# Schematic.net
KiCad netlist of a schematic drawn in EAGLE
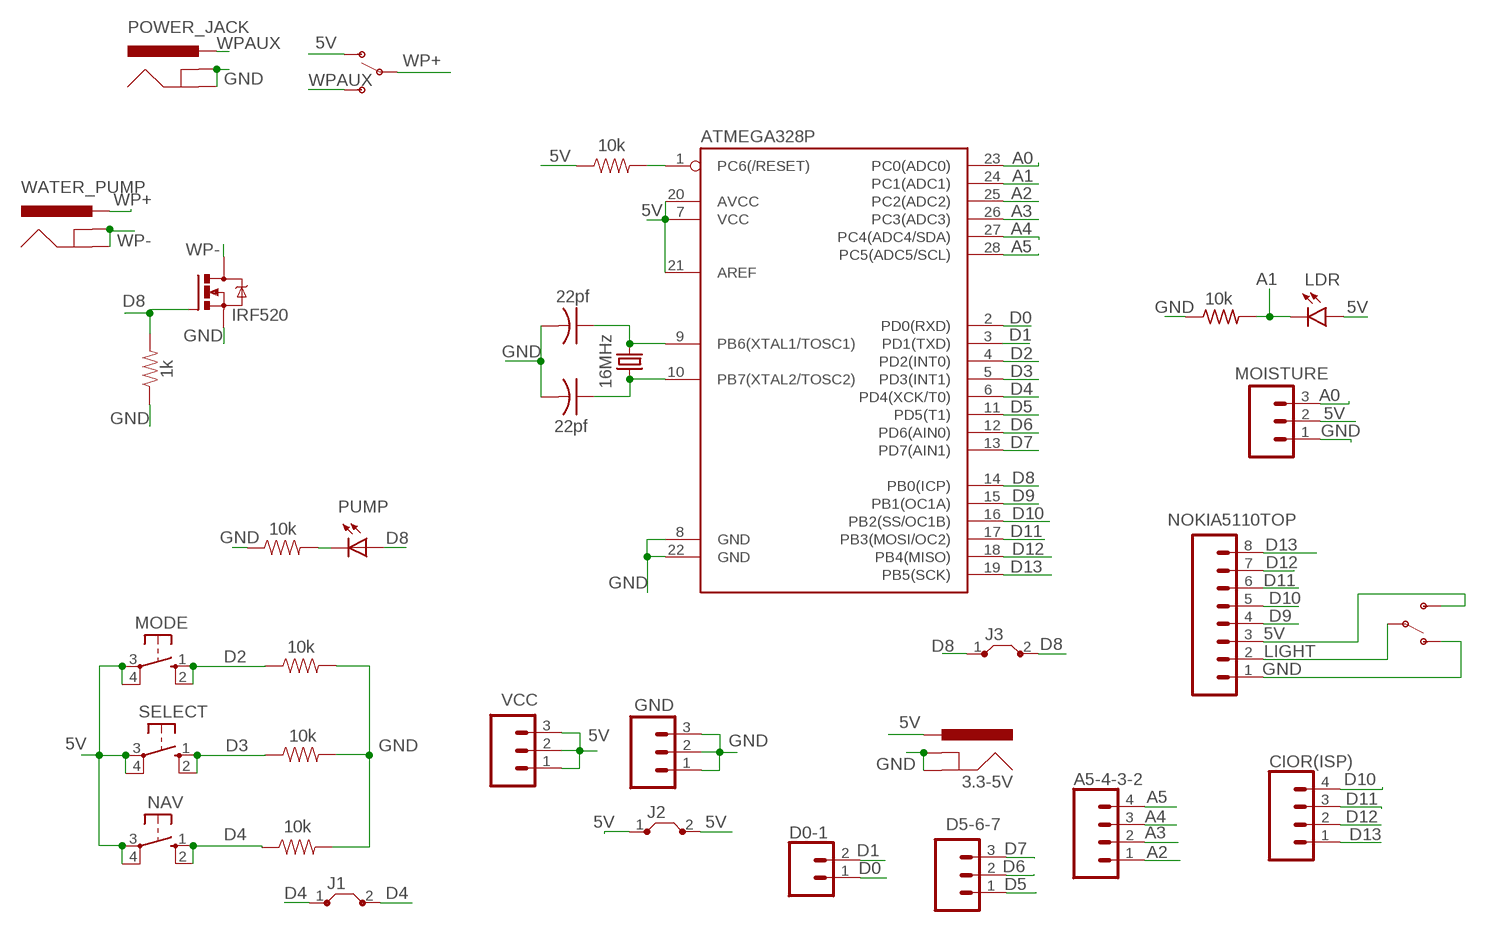
[diagram p0: schematic, sheet 1]

(export (version "E")
  (design (tool "Eeschema 10.0.6"))
  (components
    (comp (ref "3.3-5V")
      (value "POWER_JACK")
      (footprint "eagle-import:POWER_JACK_PTH")
      (libsource (lib "eagle-import") (part "POWER_JACK"))
    )
    (comp (ref "5V/AUX")
      (value "SWITCH-SPDT-PTH-11.6X4.0MM-LOCK")
      (footprint "eagle-import:SWITCH_SPDT_PTH_11.6X4.0MM_LOCK")
      (libsource (lib "eagle-import") (part "SWITCH-SPDT-PTH-11.6X4.0MM-LOCK"))
    )
    (comp (ref "A5-4-3-2")
      (value "CONN_04")
      (footprint "eagle-import:1X04")
      (libsource (lib "eagle-import") (part "CONN_04"))
    )
    (comp (ref "ATMEGA328P")
      (value "328P")
      (footprint "eagle-import:DIP28")
      (libsource (lib "eagle-import") (part "ATMEGA328P_PDIP"))
    )
    (comp (ref "AUX_POWER")
      (value "POWER_JACK")
      (footprint "eagle-import:POWER_JACK_PTH")
      (libsource (lib "eagle-import") (part "POWER_JACK"))
    )
    (comp (ref "C1")
      (value "22pf")
      (footprint "eagle-import:C025-024X044")
      (libsource (lib "eagle-import") (part "C-US025-024X044"))
    )
    (comp (ref "C2")
      (value "22pf")
      (footprint "eagle-import:C025-024X044")
      (libsource (lib "eagle-import") (part "C-US025-024X044"))
    )
    (comp (ref "CIOR(ISP)")
      (value "CONN_04")
      (footprint "eagle-import:1X04")
      (libsource (lib "eagle-import") (part "CONN_04"))
    )
    (comp (ref "D0-1")
      (value "CONN_02")
      (footprint "eagle-import:1X02")
      (libsource (lib "eagle-import") (part "CONN_02"))
    )
    (comp (ref "D5-6-7")
      (value "CONN_03")
      (footprint "eagle-import:1X03")
      (libsource (lib "eagle-import") (part "CONN_03"))
    )
    (comp (ref "GND")
      (value "CONN_03")
      (footprint "eagle-import:1X03")
      (libsource (lib "eagle-import") (part "CONN_03"))
    )
    (comp (ref "GND/VCC")
      (value "SWITCH-SPDT-PTH-11.6X4.0MM-LOCK")
      (footprint "eagle-import:SWITCH_SPDT_PTH_11.6X4.0MM_LOCK")
      (libsource (lib "eagle-import") (part "SWITCH-SPDT-PTH-11.6X4.0MM-LOCK"))
    )
    (comp (ref "J1")
      (value "J5MM")
      (footprint "eagle-import:05")
      (libsource (lib "eagle-import") (part "J5MM"))
    )
    (comp (ref "J2")
      (value "J5MM")
      (footprint "eagle-import:05")
      (libsource (lib "eagle-import") (part "J5MM"))
    )
    (comp (ref "J3")
      (value "J5MM")
      (footprint "eagle-import:05")
      (libsource (lib "eagle-import") (part "J5MM"))
    )
    (comp (ref "LDR")
      (value "LED3MM")
      (footprint "eagle-import:LED_3MM")
      (libsource (lib "eagle-import") (part "LED3MM"))
    )
    (comp (ref "MODE")
      (value "10-XX")
      (footprint "eagle-import:B3F-10XX")
      (fields (field (name "MPN") "B3F-1000"))
      (libsource (lib "eagle-import") (part "10-XX"))
    )
    (comp (ref "MOISTURE")
      (value "CONN_03")
      (footprint "eagle-import:1X03")
      (libsource (lib "eagle-import") (part "CONN_03"))
    )
    (comp (ref "NAV")
      (value "10-XX")
      (footprint "eagle-import:B3F-10XX")
      (fields (field (name "MPN") "B3F-1000"))
      (libsource (lib "eagle-import") (part "10-XX"))
    )
    (comp (ref "NOKIA5110TOP")
      (value "CONN_08\"")
      (footprint "eagle-import:1X08")
      (libsource (lib "eagle-import") (part "CONN_08{dblquote}"))
    )
    (comp (ref "PUMP")
      (value "LED5MM")
      (footprint "eagle-import:LED5MM")
      (libsource (lib "eagle-import") (part "adafruit_420_LED5MM"))
    )
    (comp (ref "Q1")
      (value "IRF520")
      (footprint "eagle-import:TO220BV")
      (libsource (lib "eagle-import") (part "IRF520"))
    )
    (comp (ref "R2")
      (value "10k")
      (footprint "eagle-import:AXIAL-0.1")
      (libsource (lib "eagle-import") (part "10KOHM-VERT-1/4W-5%"))
    )
    (comp (ref "R3")
      (value "10k")
      (footprint "eagle-import:AXIAL-0.1")
      (libsource (lib "eagle-import") (part "10KOHM-VERT-1/6W-5%"))
    )
    (comp (ref "R4")
      (value "10k")
      (footprint "eagle-import:AXIAL-0.1")
      (libsource (lib "eagle-import") (part "10KOHM-VERT-1/6W-5%"))
    )
    (comp (ref "R5")
      (value "10k")
      (footprint "eagle-import:AXIAL-0.1")
      (libsource (lib "eagle-import") (part "10KOHM-VERT-1/6W-5%"))
    )
    (comp (ref "R6")
      (value "10k")
      (footprint "eagle-import:0207_2V")
      (libsource (lib "eagle-import") (part "R-US_0207/2V"))
    )
    (comp (ref "R7")
      (value "10k")
      (footprint "eagle-import:AXIAL-0.1")
      (libsource (lib "eagle-import") (part "10KOHM-VERT-1/6W-5%"))
    )
    (comp (ref "R8")
      (value "1k")
      (footprint "eagle-import:AXIAL-0.1")
      (libsource (lib "eagle-import") (part "1KOHM-VERT-1/6W-5%"))
    )
    (comp (ref "SELECT")
      (value "10-XX")
      (footprint "eagle-import:B3F-10XX")
      (fields (field (name "MPN") "B3F-1000"))
      (libsource (lib "eagle-import") (part "10-XX"))
    )
    (comp (ref "VCC")
      (value "CONN_03")
      (footprint "eagle-import:1X03")
      (libsource (lib "eagle-import") (part "CONN_03"))
    )
    (comp (ref "WATER_PUMP")
      (value "WATER_PUMP")
      (footprint "eagle-import:POWER_JACK_PTH")
      (libsource (lib "eagle-import") (part "POWER_JACK"))
    )
    (comp (ref "Y1")
      (value "16MHz")
      (footprint "eagle-import:HC49US")
      (libsource (lib "eagle-import") (part "CRYSTAL-16MHZPTH-HC49US"))
    )
  )
  (nets
    (net (code "1") (name "/5V") (class "Default")
      (node (ref "3.3-5V") (pin "PWR") (pinfunction "PWR_PWR") (pintype "bidirectional"))
      (node (ref "5V/AUX") (pin "1") (pinfunction "O_1") (pintype "passive"))
      (node (ref "ATMEGA328P") (pin "20") (pinfunction "AVCC_20") (pintype "bidirectional"))
      (node (ref "ATMEGA328P") (pin "21") (pinfunction "AREF_21") (pintype "bidirectional"))
      (node (ref "ATMEGA328P") (pin "7") (pinfunction "VCC_7") (pintype "bidirectional"))
      (node (ref "GND/VCC") (pin "3") (pinfunction "S_3") (pintype "passive"))
      (node (ref "J2") (pin "1") (pinfunction "1_1") (pintype "passive"))
      (node (ref "J2") (pin "2") (pinfunction "2_2") (pintype "passive"))
      (node (ref "LDR") (pin "A") (pinfunction "A_A") (pintype "passive"))
      (node (ref "MODE") (pin "3") (pinfunction "P_3") (pintype "passive"))
      (node (ref "MODE") (pin "4") (pinfunction "P1_4") (pintype "passive"))
      (node (ref "MOISTURE") (pin "2") (pinfunction "2_2") (pintype "passive"))
      (node (ref "NAV") (pin "3") (pinfunction "P_3") (pintype "passive"))
      (node (ref "NAV") (pin "4") (pinfunction "P1_4") (pintype "passive"))
      (node (ref "NOKIA5110TOP") (pin "3") (pinfunction "3_3") (pintype "passive"))
      (node (ref "R7") (pin "P$1") (pinfunction "1_P$1") (pintype "passive"))
      (node (ref "SELECT") (pin "3") (pinfunction "P_3") (pintype "passive"))
      (node (ref "SELECT") (pin "4") (pinfunction "P1_4") (pintype "passive"))
      (node (ref "VCC") (pin "1") (pinfunction "1_1") (pintype "passive"))
      (node (ref "VCC") (pin "2") (pinfunction "2_2") (pintype "passive"))
      (node (ref "VCC") (pin "3") (pinfunction "3_3") (pintype "passive"))
    )
    (net (code "2") (name "/A0") (class "Default")
      (node (ref "ATMEGA328P") (pin "23") (pinfunction "PC0(ADC0)_23") (pintype "bidirectional"))
      (node (ref "MOISTURE") (pin "3") (pinfunction "3_3") (pintype "passive"))
    )
    (net (code "3") (name "/A1") (class "Default")
      (node (ref "ATMEGA328P") (pin "24") (pinfunction "PC1(ADC1)_24") (pintype "bidirectional"))
      (node (ref "LDR") (pin "K") (pinfunction "C_K") (pintype "passive"))
      (node (ref "R6") (pin "2") (pinfunction "2_2") (pintype "passive"))
    )
    (net (code "4") (name "/A2") (class "Default")
      (node (ref "A5-4-3-2") (pin "1") (pinfunction "1_1") (pintype "passive"))
      (node (ref "ATMEGA328P") (pin "25") (pinfunction "PC2(ADC2)_25") (pintype "bidirectional"))
    )
    (net (code "5") (name "/A3") (class "Default")
      (node (ref "A5-4-3-2") (pin "2") (pinfunction "2_2") (pintype "passive"))
      (node (ref "ATMEGA328P") (pin "26") (pinfunction "PC3(ADC3)_26") (pintype "bidirectional"))
    )
    (net (code "6") (name "/A4") (class "Default")
      (node (ref "A5-4-3-2") (pin "3") (pinfunction "3_3") (pintype "passive"))
      (node (ref "ATMEGA328P") (pin "27") (pinfunction "PC4(ADC4/SDA)_27") (pintype "bidirectional"))
    )
    (net (code "7") (name "/A5") (class "Default")
      (node (ref "A5-4-3-2") (pin "4") (pinfunction "4_4") (pintype "passive"))
      (node (ref "ATMEGA328P") (pin "28") (pinfunction "PC5(ADC5/SCL)_28") (pintype "bidirectional"))
    )
    (net (code "8") (name "/D0") (class "Default")
      (node (ref "ATMEGA328P") (pin "2") (pinfunction "PD0(RXD)_2") (pintype "bidirectional"))
      (node (ref "D0-1") (pin "1") (pinfunction "1_1") (pintype "passive"))
    )
    (net (code "9") (name "/D1") (class "Default")
      (node (ref "ATMEGA328P") (pin "3") (pinfunction "PD1(TXD)_3") (pintype "bidirectional"))
      (node (ref "D0-1") (pin "2") (pinfunction "2_2") (pintype "passive"))
    )
    (net (code "10") (name "/D2") (class "Default")
      (node (ref "ATMEGA328P") (pin "4") (pinfunction "PD2(INT0)_4") (pintype "bidirectional"))
      (node (ref "MODE") (pin "1") (pinfunction "S_1") (pintype "passive"))
      (node (ref "MODE") (pin "2") (pinfunction "S1_2") (pintype "passive"))
      (node (ref "R5") (pin "P$1") (pinfunction "1_P$1") (pintype "passive"))
    )
    (net (code "11") (name "/D3") (class "Default")
      (node (ref "ATMEGA328P") (pin "5") (pinfunction "PD3(INT1)_5") (pintype "bidirectional"))
      (node (ref "R4") (pin "P$1") (pinfunction "1_P$1") (pintype "passive"))
      (node (ref "SELECT") (pin "1") (pinfunction "S_1") (pintype "passive"))
      (node (ref "SELECT") (pin "2") (pinfunction "S1_2") (pintype "passive"))
    )
    (net (code "12") (name "/D4") (class "Default")
      (node (ref "ATMEGA328P") (pin "6") (pinfunction "PD4(XCK/T0)_6") (pintype "bidirectional"))
      (node (ref "J1") (pin "1") (pinfunction "1_1") (pintype "passive"))
      (node (ref "J1") (pin "2") (pinfunction "2_2") (pintype "passive"))
      (node (ref "NAV") (pin "1") (pinfunction "S_1") (pintype "passive"))
      (node (ref "NAV") (pin "2") (pinfunction "S1_2") (pintype "passive"))
      (node (ref "R3") (pin "P$1") (pinfunction "1_P$1") (pintype "passive"))
    )
    (net (code "13") (name "/D5") (class "Default")
      (node (ref "ATMEGA328P") (pin "11") (pinfunction "PD5(T1)_11") (pintype "bidirectional"))
      (node (ref "D5-6-7") (pin "1") (pinfunction "1_1") (pintype "passive"))
    )
    (net (code "14") (name "/D6") (class "Default")
      (node (ref "ATMEGA328P") (pin "12") (pinfunction "PD6(AIN0)_12") (pintype "bidirectional"))
      (node (ref "D5-6-7") (pin "2") (pinfunction "2_2") (pintype "passive"))
    )
    (net (code "15") (name "/D7") (class "Default")
      (node (ref "ATMEGA328P") (pin "13") (pinfunction "PD7(AIN1)_13") (pintype "bidirectional"))
      (node (ref "D5-6-7") (pin "3") (pinfunction "3_3") (pintype "passive"))
    )
    (net (code "16") (name "/D8") (class "Default")
      (node (ref "ATMEGA328P") (pin "14") (pinfunction "PB0(ICP)_14") (pintype "bidirectional"))
      (node (ref "J3") (pin "1") (pinfunction "1_1") (pintype "passive"))
      (node (ref "J3") (pin "2") (pinfunction "2_2") (pintype "passive"))
      (node (ref "PUMP") (pin "A") (pinfunction "A_A") (pintype "passive"))
      (node (ref "Q1") (pin "G") (pinfunction "G_G") (pintype "passive"))
      (node (ref "R8") (pin "P$2") (pinfunction "2_P$2") (pintype "passive"))
    )
    (net (code "17") (name "/D9") (class "Default")
      (node (ref "ATMEGA328P") (pin "15") (pinfunction "PB1(OC1A)_15") (pintype "bidirectional"))
      (node (ref "NOKIA5110TOP") (pin "4") (pinfunction "4_4") (pintype "passive"))
    )
    (net (code "18") (name "/D10") (class "Default")
      (node (ref "ATMEGA328P") (pin "16") (pinfunction "PB2(SS/OC1B)_16") (pintype "bidirectional"))
      (node (ref "CIOR(ISP)") (pin "4") (pinfunction "4_4") (pintype "passive"))
      (node (ref "NOKIA5110TOP") (pin "5") (pinfunction "5_5") (pintype "passive"))
    )
    (net (code "19") (name "/D11") (class "Default")
      (node (ref "ATMEGA328P") (pin "17") (pinfunction "PB3(MOSI/OC2)_17") (pintype "bidirectional"))
      (node (ref "CIOR(ISP)") (pin "3") (pinfunction "3_3") (pintype "passive"))
      (node (ref "NOKIA5110TOP") (pin "6") (pinfunction "6_6") (pintype "passive"))
    )
    (net (code "20") (name "/D12") (class "Default")
      (node (ref "ATMEGA328P") (pin "18") (pinfunction "PB4(MISO)_18") (pintype "bidirectional"))
      (node (ref "CIOR(ISP)") (pin "2") (pinfunction "2_2") (pintype "passive"))
      (node (ref "NOKIA5110TOP") (pin "7") (pinfunction "7_7") (pintype "passive"))
    )
    (net (code "21") (name "/D13") (class "Default")
      (node (ref "ATMEGA328P") (pin "19") (pinfunction "PB5(SCK)_19") (pintype "bidirectional"))
      (node (ref "CIOR(ISP)") (pin "1") (pinfunction "1_1") (pintype "passive"))
      (node (ref "NOKIA5110TOP") (pin "8") (pinfunction "8_8") (pintype "passive"))
    )
    (net (code "22") (name "/GND") (class "Default")
      (node (ref "3.3-5V") (pin "GND") (pinfunction "GND_GND") (pintype "bidirectional"))
      (node (ref "3.3-5V") (pin "GNDBREAK") (pinfunction "GNDBREAK_GNDBREAK") (pintype "bidirectional"))
      (node (ref "ATMEGA328P") (pin "22") (pinfunction "GND_22") (pintype "bidirectional"))
      (node (ref "ATMEGA328P") (pin "8") (pinfunction "GND_8") (pintype "bidirectional"))
      (node (ref "AUX_POWER") (pin "GND") (pinfunction "GND_GND") (pintype "bidirectional"))
      (node (ref "AUX_POWER") (pin "GNDBREAK") (pinfunction "GNDBREAK_GNDBREAK") (pintype "bidirectional"))
      (node (ref "C1") (pin "2") (pinfunction "2_2") (pintype "passive"))
      (node (ref "C2") (pin "2") (pinfunction "2_2") (pintype "passive"))
      (node (ref "GND") (pin "1") (pinfunction "1_1") (pintype "passive"))
      (node (ref "GND") (pin "2") (pinfunction "2_2") (pintype "passive"))
      (node (ref "GND") (pin "3") (pinfunction "3_3") (pintype "passive"))
      (node (ref "GND/VCC") (pin "1") (pinfunction "O_1") (pintype "passive"))
      (node (ref "MOISTURE") (pin "1") (pinfunction "1_1") (pintype "passive"))
      (node (ref "NOKIA5110TOP") (pin "1") (pinfunction "1_1") (pintype "passive"))
      (node (ref "Q1") (pin "S") (pinfunction "S_S") (pintype "passive"))
      (node (ref "R2") (pin "P$1") (pinfunction "1_P$1") (pintype "passive"))
      (node (ref "R3") (pin "P$2") (pinfunction "2_P$2") (pintype "passive"))
      (node (ref "R4") (pin "P$2") (pinfunction "2_P$2") (pintype "passive"))
      (node (ref "R5") (pin "P$2") (pinfunction "2_P$2") (pintype "passive"))
      (node (ref "R6") (pin "1") (pinfunction "1_1") (pintype "passive"))
      (node (ref "R8") (pin "P$1") (pinfunction "1_P$1") (pintype "passive"))
    )
    (net (code "23") (name "/LIGHT") (class "Default")
      (node (ref "GND/VCC") (pin "2") (pinfunction "P_2") (pintype "passive"))
      (node (ref "NOKIA5110TOP") (pin "2") (pinfunction "2_2") (pintype "passive"))
    )
    (net (code "24") (name "/WP+") (class "Default")
      (node (ref "5V/AUX") (pin "2") (pinfunction "P_2") (pintype "passive"))
      (node (ref "WATER_PUMP") (pin "PWR") (pinfunction "PWR_PWR") (pintype "bidirectional"))
    )
    (net (code "25") (name "/WP-") (class "Default")
      (node (ref "Q1") (pin "D") (pinfunction "D_D") (pintype "passive"))
      (node (ref "WATER_PUMP") (pin "GND") (pinfunction "GND_GND") (pintype "bidirectional"))
      (node (ref "WATER_PUMP") (pin "GNDBREAK") (pinfunction "GNDBREAK_GNDBREAK") (pintype "bidirectional"))
    )
    (net (code "26") (name "/WPAUX") (class "Default")
      (node (ref "5V/AUX") (pin "3") (pinfunction "S_3") (pintype "passive"))
      (node (ref "AUX_POWER") (pin "PWR") (pinfunction "PWR_PWR") (pintype "bidirectional"))
    )
    (net (code "27") (name "Net-(ATMEGA328P-PB6(XTAL1{slash}TOSC1))") (class "Default")
      (node (ref "ATMEGA328P") (pin "9") (pinfunction "PB6(XTAL1/TOSC1)_9") (pintype "bidirectional"))
      (node (ref "C1") (pin "1") (pinfunction "1_1") (pintype "passive"))
      (node (ref "Y1") (pin "2") (pinfunction "2_2") (pintype "passive"))
    )
    (net (code "28") (name "Net-(ATMEGA328P-PB7(XTAL2{slash}TOSC2))") (class "Default")
      (node (ref "ATMEGA328P") (pin "10") (pinfunction "PB7(XTAL2/TOSC2)_10") (pintype "bidirectional"))
      (node (ref "C2") (pin "1") (pinfunction "1_1") (pintype "passive"))
      (node (ref "Y1") (pin "1") (pinfunction "1_1") (pintype "passive"))
    )
    (net (code "29") (name "Net-(ATMEGA328P-PC6({slash}RESET))") (class "Default")
      (node (ref "ATMEGA328P") (pin "1") (pinfunction "PC6(/RESET)_1") (pintype "bidirectional"))
      (node (ref "R7") (pin "P$2") (pinfunction "2_P$2") (pintype "passive"))
    )
    (net (code "30") (name "Net-(PUMP-C)") (class "Default")
      (node (ref "PUMP") (pin "K") (pinfunction "C_K") (pintype "passive"))
      (node (ref "R2") (pin "P$2") (pinfunction "2_P$2") (pintype "passive"))
    )
  )
)
